# ardunio-physics-board-v3.net
KiCad netlist of a schematic drawn in EAGLE
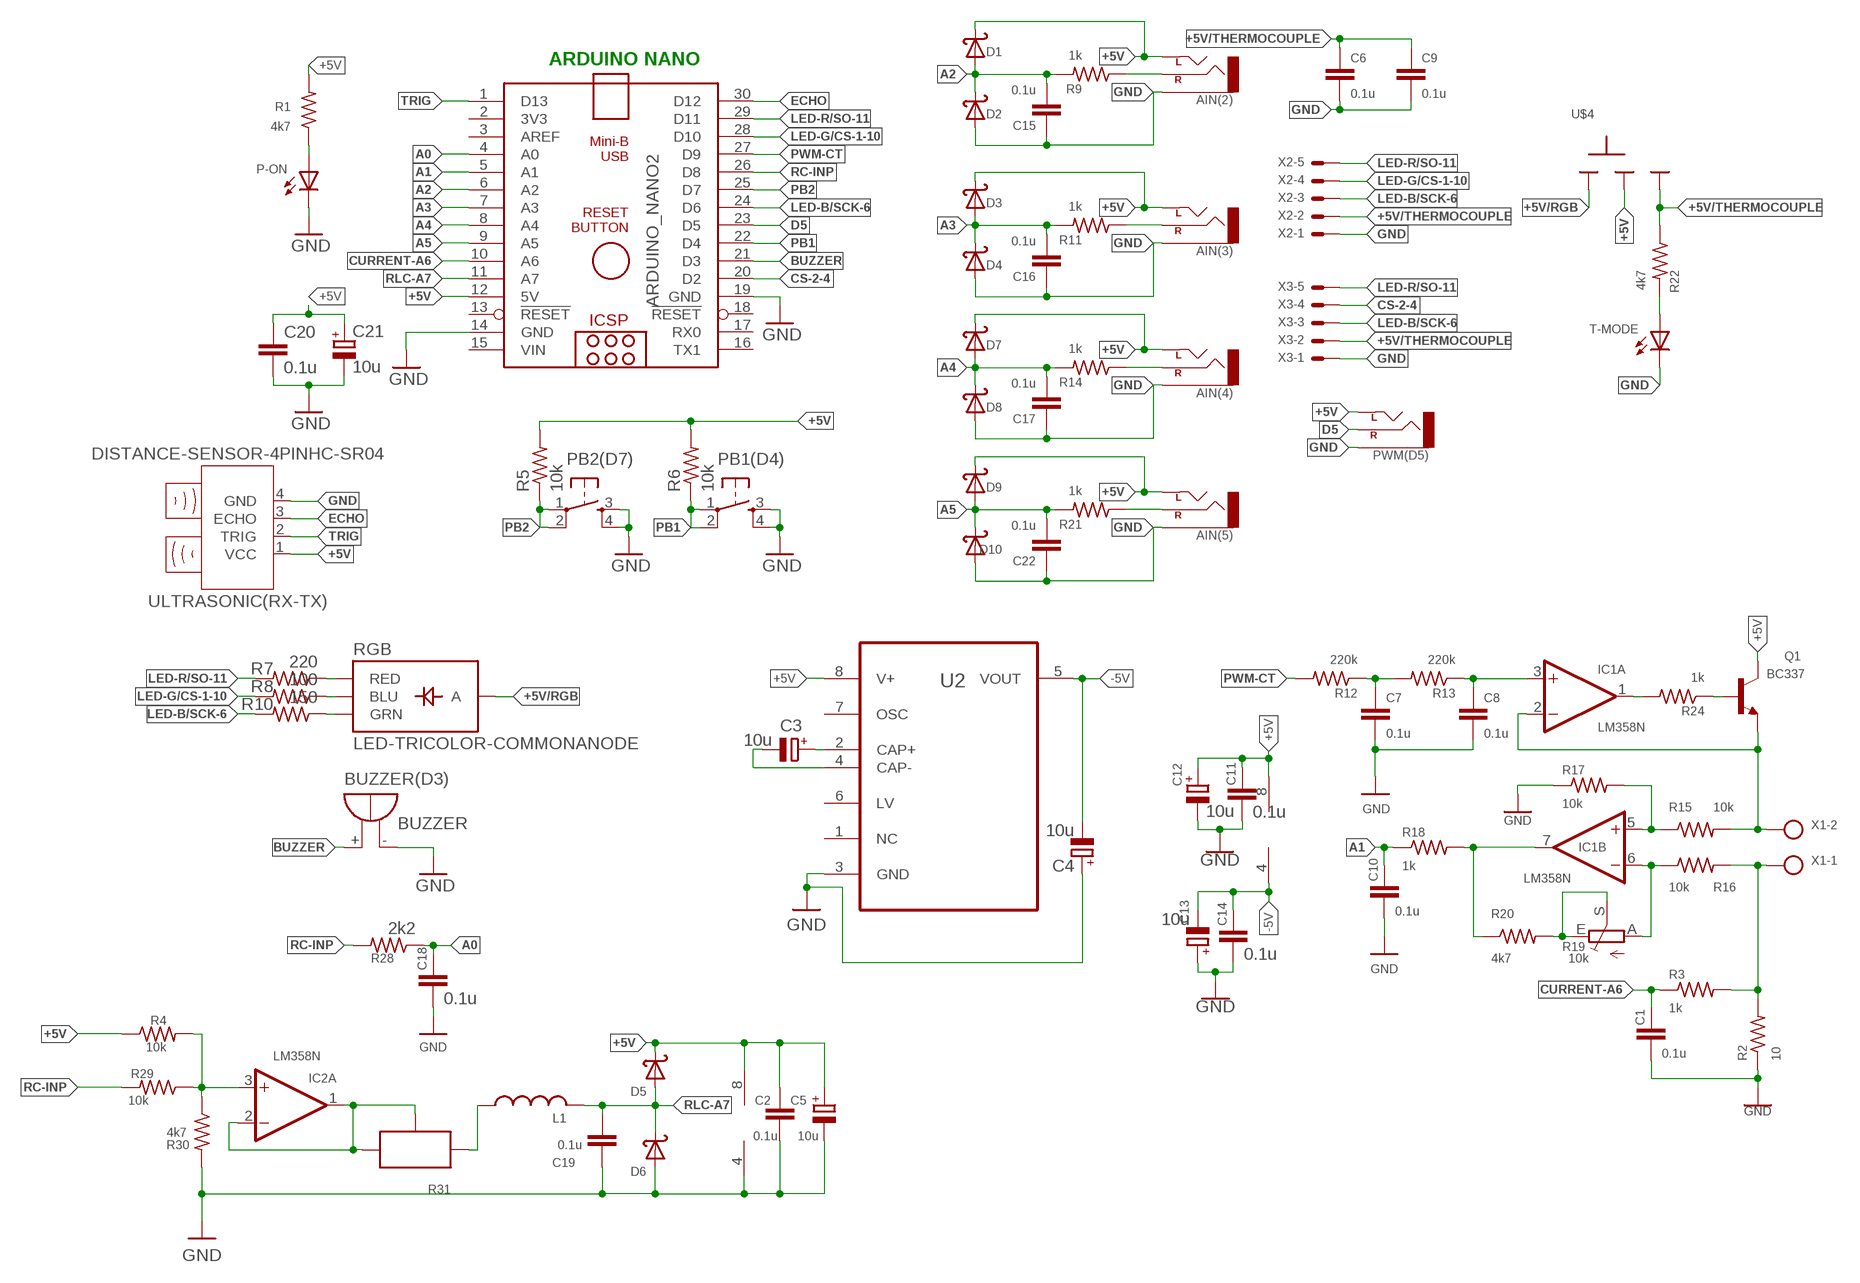
[diagram p0: schematic, sheet 1]

(export (version "E")
  (design (tool "Eeschema 10.0.6"))
  (components
    (comp (ref "AIN(2)")
      (value "AUX-CONNECTOR_CEDT_JANUARY_2015_V5_AUDIO-JACKPTH")
      (footprint "eagle-import:AUX-CONNECTOR_CEDT_JANUARY_2015_V5_AUDIO-JACK")
      (libsource (lib "eagle-import") (part "AUX-CONNECTOR_CEDT_JANUARY_2015_V5_AUDIO-JACKPTH"))
    )
    (comp (ref "AIN(3)")
      (value "AUX-CONNECTOR_CEDT_JANUARY_2015_V5_AUDIO-JACKPTH")
      (footprint "eagle-import:AUX-CONNECTOR_CEDT_JANUARY_2015_V5_AUDIO-JACK")
      (libsource (lib "eagle-import") (part "AUX-CONNECTOR_CEDT_JANUARY_2015_V5_AUDIO-JACKPTH"))
    )
    (comp (ref "AIN(4)")
      (value "AUX-CONNECTOR_CEDT_JANUARY_2015_V5_AUDIO-JACKPTH")
      (footprint "eagle-import:AUX-CONNECTOR_CEDT_JANUARY_2015_V5_AUDIO-JACK")
      (libsource (lib "eagle-import") (part "AUX-CONNECTOR_CEDT_JANUARY_2015_V5_AUDIO-JACKPTH"))
    )
    (comp (ref "AIN(5)")
      (value "AUX-CONNECTOR_CEDT_JANUARY_2015_V5_AUDIO-JACKPTH")
      (footprint "eagle-import:AUX-CONNECTOR_CEDT_JANUARY_2015_V5_AUDIO-JACK")
      (libsource (lib "eagle-import") (part "AUX-CONNECTOR_CEDT_JANUARY_2015_V5_AUDIO-JACKPTH"))
    )
    (comp (ref "ARDUINO_NANO2")
      (value "ARDUINONANOV30_ARDUINO_NANO")
      (footprint "eagle-import:ARDUINONANOV30_ARDUINO_NANO")
      (libsource (lib "eagle-import") (part "ARDUINONANOV30_ARDUINO_NANO"))
    )
    (comp (ref "BUZZER(D3)")
      (value "BUZZER")
      (footprint "eagle-import:F_TMB")
      (libsource (lib "eagle-import") (part "BUZZER"))
    )
    (comp (ref "C1")
      (value "0.1u")
      (footprint "eagle-import:C025-025X050")
      (libsource (lib "eagle-import") (part "C-EU025-025X050"))
    )
    (comp (ref "C2")
      (value "0.1u")
      (footprint "eagle-import:C025-025X050")
      (libsource (lib "eagle-import") (part "C-EU025-025X050"))
    )
    (comp (ref "C3")
      (value "10u")
      (footprint "eagle-import:TT2D5")
      (libsource (lib "eagle-import") (part "CPOL-EUTT2D5"))
    )
    (comp (ref "C4")
      (value "10u")
      (footprint "eagle-import:TT2D5")
      (libsource (lib "eagle-import") (part "CPOL-EUTT2D5"))
    )
    (comp (ref "C5")
      (value "10u")
      (footprint "eagle-import:TT2D5")
      (libsource (lib "eagle-import") (part "CPOL-EUTT2D5"))
    )
    (comp (ref "C6")
      (value "0.1u")
      (footprint "eagle-import:C025-024X044")
      (libsource (lib "eagle-import") (part "C-EU025-024X044"))
    )
    (comp (ref "C7")
      (value "0.1u")
      (footprint "eagle-import:C025-025X050")
      (libsource (lib "eagle-import") (part "C-EU025-025X050"))
    )
    (comp (ref "C8")
      (value "0.1u")
      (footprint "eagle-import:C025-025X050")
      (libsource (lib "eagle-import") (part "C-EU025-025X050"))
    )
    (comp (ref "C9")
      (value "0.1u")
      (footprint "eagle-import:C025-024X044")
      (libsource (lib "eagle-import") (part "C-EU025-024X044"))
    )
    (comp (ref "C10")
      (value "0.1u")
      (footprint "eagle-import:C025-025X050")
      (libsource (lib "eagle-import") (part "C-EU025-025X050"))
    )
    (comp (ref "C11")
      (value "0.1u")
      (footprint "eagle-import:C025-025X050")
      (libsource (lib "eagle-import") (part "C-EU025-025X050"))
    )
    (comp (ref "C12")
      (value "10u")
      (footprint "eagle-import:TT2D5")
      (libsource (lib "eagle-import") (part "CPOL-EUTT2D5"))
    )
    (comp (ref "C13")
      (value "10u")
      (footprint "eagle-import:TT2D5")
      (libsource (lib "eagle-import") (part "CPOL-EUTT2D5"))
    )
    (comp (ref "C14")
      (value "0.1u")
      (footprint "eagle-import:C025-025X050")
      (libsource (lib "eagle-import") (part "C-EU025-025X050"))
    )
    (comp (ref "C15")
      (value "0.1u")
      (footprint "eagle-import:C025-024X044")
      (libsource (lib "eagle-import") (part "C-EU025-024X044"))
    )
    (comp (ref "C16")
      (value "0.1u")
      (footprint "eagle-import:C025-024X044")
      (libsource (lib "eagle-import") (part "C-EU025-024X044"))
    )
    (comp (ref "C17")
      (value "0.1u")
      (footprint "eagle-import:C025-024X044")
      (libsource (lib "eagle-import") (part "C-EU025-024X044"))
    )
    (comp (ref "C18")
      (value "0.1u")
      (footprint "eagle-import:C025-025X050")
      (libsource (lib "eagle-import") (part "C-EU025-025X050"))
    )
    (comp (ref "C19")
      (value "0.1u")
      (footprint "eagle-import:C025-025X050")
      (libsource (lib "eagle-import") (part "C-EU025-025X050"))
    )
    (comp (ref "C20")
      (value "0.1u")
      (footprint "eagle-import:C025-024X044")
      (libsource (lib "eagle-import") (part "C-EU025-024X044"))
    )
    (comp (ref "C21")
      (value "10u")
      (footprint "eagle-import:E2,5-5")
      (libsource (lib "eagle-import") (part "CPOL-EUE2.5-5"))
    )
    (comp (ref "C22")
      (value "0.1u")
      (footprint "eagle-import:C025-024X044")
      (libsource (lib "eagle-import") (part "C-EU025-024X044"))
    )
    (comp (ref "D1")
      (value "1N5819")
      (footprint "eagle-import:DO41-10")
      (libsource (lib "eagle-import") (part "1N5819"))
    )
    (comp (ref "D2")
      (value "1N5819")
      (footprint "eagle-import:DO41-10")
      (libsource (lib "eagle-import") (part "1N5819"))
    )
    (comp (ref "D3")
      (value "1N5819")
      (footprint "eagle-import:DO41-10")
      (libsource (lib "eagle-import") (part "1N5819"))
    )
    (comp (ref "D4")
      (value "1N5819")
      (footprint "eagle-import:DO41-10")
      (libsource (lib "eagle-import") (part "1N5819"))
    )
    (comp (ref "D5")
      (value "1N5819")
      (footprint "eagle-import:DO41-10")
      (libsource (lib "eagle-import") (part "1N5819"))
    )
    (comp (ref "D6")
      (value "1N5819")
      (footprint "eagle-import:DO41-10")
      (libsource (lib "eagle-import") (part "1N5819"))
    )
    (comp (ref "D7")
      (value "1N5819")
      (footprint "eagle-import:DO41-10")
      (libsource (lib "eagle-import") (part "1N5819"))
    )
    (comp (ref "D8")
      (value "1N5819")
      (footprint "eagle-import:DO41-10")
      (libsource (lib "eagle-import") (part "1N5819"))
    )
    (comp (ref "D9")
      (value "1N5819")
      (footprint "eagle-import:DO41-10")
      (libsource (lib "eagle-import") (part "1N5819"))
    )
    (comp (ref "D10")
      (value "1N5819")
      (footprint "eagle-import:DO41-10")
      (libsource (lib "eagle-import") (part "1N5819"))
    )
    (comp (ref "IC1")
      (value "LM358N")
      (footprint "eagle-import:DIL08")
      (libsource (lib "eagle-import") (part "LM358N"))
    )
    (comp (ref "IC2")
      (value "LM358N")
      (footprint "eagle-import:DIL08")
      (libsource (lib "eagle-import") (part "LM358N"))
    )
    (comp (ref "L1")
      (value "L-US6000-XXX-RC")
      (footprint "eagle-import:6000-XXXX-RC")
      (libsource (lib "eagle-import") (part "L-US6000-XXX-RC"))
    )
    (comp (ref "P-ON")
      (value "LED3MM")
      (footprint "eagle-import:LED3MM")
      (libsource (lib "eagle-import") (part "LED3MM"))
    )
    (comp (ref "PB1(D4)")
      (value "OMRON_SWITCH_40-XX")
      (footprint "eagle-import:B3F-40XX")
      (libsource (lib "eagle-import") (part "OMRON_SWITCH_40-XX"))
    )
    (comp (ref "PB2(D7)")
      (value "OMRON_SWITCH_40-XX")
      (footprint "eagle-import:B3F-40XX")
      (libsource (lib "eagle-import") (part "OMRON_SWITCH_40-XX"))
    )
    (comp (ref "PWM(D5)")
      (value "AUX-CONNECTOR_CEDT_JANUARY_2015_V5_AUDIO-JACKPTH")
      (footprint "eagle-import:AUX-CONNECTOR_CEDT_JANUARY_2015_V5_AUDIO-JACK")
      (libsource (lib "eagle-import") (part "AUX-CONNECTOR_CEDT_JANUARY_2015_V5_AUDIO-JACKPTH"))
    )
    (comp (ref "Q1")
      (value "BC337")
      (footprint "eagle-import:TO92")
      (libsource (lib "eagle-import") (part "BC337"))
    )
    (comp (ref "R1")
      (value "4k7")
      (footprint "eagle-import:0204_7")
      (libsource (lib "eagle-import") (part "R-US_0204/7"))
    )
    (comp (ref "R2")
      (value "10")
      (footprint "eagle-import:0207_10")
      (libsource (lib "eagle-import") (part "RESISTOR0207/10"))
    )
    (comp (ref "R3")
      (value "1k")
      (footprint "eagle-import:0204_7")
      (libsource (lib "eagle-import") (part "R-US_0204/7"))
    )
    (comp (ref "R4")
      (value "10k")
      (footprint "eagle-import:0207_10")
      (libsource (lib "eagle-import") (part "R-US_0207/10"))
    )
    (comp (ref "R5")
      (value "10k")
      (footprint "eagle-import:0204_7")
      (libsource (lib "eagle-import") (part "R-US_0204/7"))
    )
    (comp (ref "R6")
      (value "10k")
      (footprint "eagle-import:0204_7")
      (libsource (lib "eagle-import") (part "R-US_0204/7"))
    )
    (comp (ref "R7")
      (value "220")
      (footprint "eagle-import:0207_10")
      (libsource (lib "eagle-import") (part "R-US_0207/10"))
    )
    (comp (ref "R8")
      (value "100")
      (footprint "eagle-import:0207_10")
      (libsource (lib "eagle-import") (part "R-US_0207/10"))
    )
    (comp (ref "R9")
      (value "1k")
      (footprint "eagle-import:0204_7")
      (libsource (lib "eagle-import") (part "R-US_0204/7"))
    )
    (comp (ref "R10")
      (value "150")
      (footprint "eagle-import:0207_10")
      (libsource (lib "eagle-import") (part "R-US_0207/10"))
    )
    (comp (ref "R11")
      (value "1k")
      (footprint "eagle-import:0204_7")
      (libsource (lib "eagle-import") (part "R-US_0204/7"))
    )
    (comp (ref "R12")
      (value "220k")
      (footprint "eagle-import:0207_10")
      (libsource (lib "eagle-import") (part "R-US_0207/10"))
    )
    (comp (ref "R13")
      (value "220k")
      (footprint "eagle-import:0204_7")
      (libsource (lib "eagle-import") (part "R-US_0204/7"))
    )
    (comp (ref "R14")
      (value "1k")
      (footprint "eagle-import:0204_7")
      (libsource (lib "eagle-import") (part "R-US_0204/7"))
    )
    (comp (ref "R15")
      (value "10k")
      (footprint "eagle-import:0204_7")
      (libsource (lib "eagle-import") (part "R-US_0204/7"))
    )
    (comp (ref "R16")
      (value "10k")
      (footprint "eagle-import:0204_7")
      (libsource (lib "eagle-import") (part "R-US_0204/7"))
    )
    (comp (ref "R17")
      (value "10k")
      (footprint "eagle-import:0204_7")
      (libsource (lib "eagle-import") (part "R-US_0204/7"))
    )
    (comp (ref "R18")
      (value "1k")
      (footprint "eagle-import:0204_7")
      (libsource (lib "eagle-import") (part "R-US_0204/7"))
    )
    (comp (ref "R19")
      (value "10k")
      (footprint "eagle-import:RJ9W")
      (libsource (lib "eagle-import") (part "TRIM_EU-RJ9W"))
    )
    (comp (ref "R20")
      (value "4k7")
      (footprint "eagle-import:0204_7")
      (libsource (lib "eagle-import") (part "R-US_0204/7"))
    )
    (comp (ref "R21")
      (value "1k")
      (footprint "eagle-import:0204_7")
      (libsource (lib "eagle-import") (part "R-US_0204/7"))
    )
    (comp (ref "R22")
      (value "4k7")
      (footprint "eagle-import:0204_7")
      (libsource (lib "eagle-import") (part "R-US_0204/7"))
    )
    (comp (ref "R24")
      (value "1k")
      (footprint "eagle-import:0204_7")
      (libsource (lib "eagle-import") (part "R-US_0204/7"))
    )
    (comp (ref "R28")
      (value "2k2")
      (footprint "eagle-import:0207_10")
      (libsource (lib "eagle-import") (part "R-US_0207/10"))
    )
    (comp (ref "R29")
      (value "10k")
      (footprint "eagle-import:0204_7")
      (libsource (lib "eagle-import") (part "R-US_0204/7"))
    )
    (comp (ref "R30")
      (value "4k7")
      (footprint "eagle-import:0207_10")
      (libsource (lib "eagle-import") (part "R-US_0207/10"))
    )
    (comp (ref "R31")
      (value "POTNORMAL")
      (footprint "eagle-import:RJ9W")
      (libsource (lib "eagle-import") (part "POTNORMAL"))
    )
    (comp (ref "RGB")
      (value "LED-TRICOLOR-COMMONANODE")
      (footprint "eagle-import:LED-TRICOLOR-THROUGHHOLE")
      (libsource (lib "eagle-import") (part "LED-TRICOLOR-COMMONANODE"))
    )
    (comp (ref "T-MODE")
      (value "LED3MM")
      (footprint "eagle-import:LED3MM")
      (libsource (lib "eagle-import") (part "LED3MM"))
    )
    (comp (ref "U$4")
      (value "SLIDESWITCH-BIG")
      (footprint "eagle-import:BIGSWITCH")
      (libsource (lib "eagle-import") (part "SLIDESWITCH-BIG"))
    )
    (comp (ref "U2")
      (value "ICL7660CPAZ_ICL7660CPAZ")
      (footprint "eagle-import:ICL7660CPAZ_DIP254P762X533-8")
      (fields (field (name "MF") "Renesas Electronics") (field (name "MP") "ICL7660CPAZ"))
      (libsource (lib "eagle-import") (part "ICL7660CPAZ_ICL7660CPAZ"))
    )
    (comp (ref "ULTRASONIC(RX-TX)")
      (value "DISTANCE-SENSOR-4PINHC-SR04")
      (footprint "eagle-import:HC-SR04")
      (libsource (lib "eagle-import") (part "DISTANCE-SENSOR-4PINHC-SR04"))
    )
    (comp (ref "X1")
      (value "AK500/2-H")
      (footprint "eagle-import:AK500_2-H")
      (libsource (lib "eagle-import") (part "AK500/2-H"))
    )
    (comp (ref "X2")
      (value "JST-XH-05-PIN-LONG-PAD")
      (footprint "eagle-import:JST-XH-05-PACKAGE-LONG-PAD")
      (libsource (lib "eagle-import") (part "JST-XH-05-PIN-LONG-PAD"))
    )
    (comp (ref "X3")
      (value "JST-XH-05-PIN-LONG-PAD")
      (footprint "eagle-import:JST-XH-05-PACKAGE-LONG-PAD")
      (libsource (lib "eagle-import") (part "JST-XH-05-PIN-LONG-PAD"))
    )
  )
  (nets
    (net (code "1") (name "+5V") (class "Default")
      (node (ref "AIN(2)") (pin "TIP") (pinfunction "LEFT_TIP") (pintype "bidirectional"))
      (node (ref "AIN(3)") (pin "TIP") (pinfunction "LEFT_TIP") (pintype "bidirectional"))
      (node (ref "AIN(4)") (pin "TIP") (pinfunction "LEFT_TIP") (pintype "bidirectional"))
      (node (ref "AIN(5)") (pin "TIP") (pinfunction "LEFT_TIP") (pintype "bidirectional"))
      (node (ref "ARDUINO_NANO2") (pin "12") (pinfunction "5V_12") (pintype "power_in"))
      (node (ref "C11") (pin "1") (pinfunction "1_1") (pintype "passive"))
      (node (ref "C12") (pin "+") (pinfunction "+_+") (pintype "passive"))
      (node (ref "C2") (pin "1") (pinfunction "1_1") (pintype "passive"))
      (node (ref "C20") (pin "1") (pinfunction "1_1") (pintype "passive"))
      (node (ref "C21") (pin "+") (pinfunction "+_+") (pintype "passive"))
      (node (ref "C5") (pin "+") (pinfunction "+_+") (pintype "passive"))
      (node (ref "D1") (pin "C") (pinfunction "C_C") (pintype "passive"))
      (node (ref "D3") (pin "C") (pinfunction "C_C") (pintype "passive"))
      (node (ref "D5") (pin "C") (pinfunction "C_C") (pintype "passive"))
      (node (ref "D7") (pin "C") (pinfunction "C_C") (pintype "passive"))
      (node (ref "D9") (pin "C") (pinfunction "C_C") (pintype "passive"))
      (node (ref "IC1") (pin "8") (pinfunction "V+_8") (pintype "power_in"))
      (node (ref "IC2") (pin "8") (pinfunction "V+_8") (pintype "power_in"))
      (node (ref "PWM(D5)") (pin "TIP") (pinfunction "LEFT_TIP") (pintype "bidirectional"))
      (node (ref "Q1") (pin "3") (pinfunction "C_3") (pintype "passive"))
      (node (ref "R1") (pin "2") (pinfunction "2_2") (pintype "passive"))
      (node (ref "R4") (pin "1") (pinfunction "1_1") (pintype "passive"))
      (node (ref "R5") (pin "2") (pinfunction "2_2") (pintype "passive"))
      (node (ref "R6") (pin "2") (pinfunction "2_2") (pintype "passive"))
      (node (ref "U$4") (pin "2") (pinfunction "2_2") (pintype "bidirectional"))
      (node (ref "U2") (pin "8") (pinfunction "V+_8") (pintype "power_in"))
      (node (ref "ULTRASONIC(RX-TX)") (pin "1") (pinfunction "VCC_1") (pintype "bidirectional"))
    )
    (net (code "2") (name "+5V{slash}RGB") (class "Default")
      (node (ref "RGB") (pin "ANODE") (pinfunction "A_ANODE") (pintype "bidirectional"))
      (node (ref "U$4") (pin "1") (pinfunction "1_1") (pintype "bidirectional"))
    )
    (net (code "3") (name "+5V{slash}THERMOCOUPLE") (class "Default")
      (node (ref "C6") (pin "1") (pinfunction "1_1") (pintype "passive"))
      (node (ref "C9") (pin "1") (pinfunction "1_1") (pintype "passive"))
      (node (ref "R22") (pin "1") (pinfunction "1_1") (pintype "passive"))
      (node (ref "U$4") (pin "3") (pinfunction "3_3") (pintype "bidirectional"))
      (node (ref "X2") (pin "2") (pinfunction "S_2") (pintype "passive"))
      (node (ref "X3") (pin "2") (pinfunction "S_2") (pintype "passive"))
    )
    (net (code "4") (name "-5V") (class "Default")
      (node (ref "C13") (pin "-") (pinfunction "-_-") (pintype "passive"))
      (node (ref "C14") (pin "1") (pinfunction "1_1") (pintype "passive"))
      (node (ref "C4") (pin "-") (pinfunction "-_-") (pintype "passive"))
      (node (ref "IC1") (pin "4") (pinfunction "V-_4") (pintype "power_in"))
      (node (ref "U2") (pin "5") (pinfunction "VOUT_5") (pintype "output"))
    )
    (net (code "5") (name "/VIN") (class "Default")
      (node (ref "ARDUINO_NANO2") (pin "15") (pinfunction "VIN_15") (pintype "power_in"))
    )
    (net (code "6") (name "A0") (class "Default")
      (node (ref "ARDUINO_NANO2") (pin "4") (pinfunction "A0_4") (pintype "bidirectional"))
      (node (ref "C18") (pin "1") (pinfunction "1_1") (pintype "passive"))
      (node (ref "R28") (pin "1") (pinfunction "1_1") (pintype "passive"))
    )
    (net (code "7") (name "A1") (class "Default")
      (node (ref "ARDUINO_NANO2") (pin "5") (pinfunction "A1_5") (pintype "bidirectional"))
      (node (ref "C10") (pin "1") (pinfunction "1_1") (pintype "passive"))
      (node (ref "R18") (pin "1") (pinfunction "1_1") (pintype "passive"))
    )
    (net (code "8") (name "A2") (class "Default")
      (node (ref "ARDUINO_NANO2") (pin "6") (pinfunction "A2_6") (pintype "bidirectional"))
      (node (ref "C15") (pin "2") (pinfunction "2_2") (pintype "passive"))
      (node (ref "D1") (pin "A") (pinfunction "A_A") (pintype "passive"))
      (node (ref "D2") (pin "C") (pinfunction "C_C") (pintype "passive"))
      (node (ref "R9") (pin "2") (pinfunction "2_2") (pintype "passive"))
    )
    (net (code "9") (name "A3") (class "Default")
      (node (ref "ARDUINO_NANO2") (pin "7") (pinfunction "A3_7") (pintype "bidirectional"))
      (node (ref "C16") (pin "2") (pinfunction "2_2") (pintype "passive"))
      (node (ref "D3") (pin "A") (pinfunction "A_A") (pintype "passive"))
      (node (ref "D4") (pin "C") (pinfunction "C_C") (pintype "passive"))
      (node (ref "R11") (pin "2") (pinfunction "2_2") (pintype "passive"))
    )
    (net (code "10") (name "A4") (class "Default")
      (node (ref "ARDUINO_NANO2") (pin "8") (pinfunction "A4_8") (pintype "bidirectional"))
      (node (ref "C17") (pin "2") (pinfunction "2_2") (pintype "passive"))
      (node (ref "D7") (pin "A") (pinfunction "A_A") (pintype "passive"))
      (node (ref "D8") (pin "C") (pinfunction "C_C") (pintype "passive"))
      (node (ref "R14") (pin "2") (pinfunction "2_2") (pintype "passive"))
    )
    (net (code "11") (name "A5") (class "Default")
      (node (ref "ARDUINO_NANO2") (pin "9") (pinfunction "A5_9") (pintype "bidirectional"))
      (node (ref "C22") (pin "2") (pinfunction "2_2") (pintype "passive"))
      (node (ref "D10") (pin "C") (pinfunction "C_C") (pintype "passive"))
      (node (ref "D9") (pin "A") (pinfunction "A_A") (pintype "passive"))
      (node (ref "R21") (pin "2") (pinfunction "2_2") (pintype "passive"))
    )
    (net (code "12") (name "BUZZER") (class "Default")
      (node (ref "ARDUINO_NANO2") (pin "21") (pinfunction "D3_21") (pintype "bidirectional"))
      (node (ref "BUZZER(D3)") (pin "+") (pinfunction "+_+") (pintype "passive"))
    )
    (net (code "13") (name "CS-2-4") (class "Default")
      (node (ref "ARDUINO_NANO2") (pin "20") (pinfunction "D2_20") (pintype "bidirectional"))
      (node (ref "X3") (pin "4") (pinfunction "S_4") (pintype "passive"))
    )
    (net (code "14") (name "CURRENT-A6") (class "Default")
      (node (ref "ARDUINO_NANO2") (pin "10") (pinfunction "A6_10") (pintype "bidirectional"))
      (node (ref "C1") (pin "1") (pinfunction "1_1") (pintype "passive"))
      (node (ref "R3") (pin "1") (pinfunction "1_1") (pintype "passive"))
    )
    (net (code "15") (name "D5") (class "Default")
      (node (ref "ARDUINO_NANO2") (pin "23") (pinfunction "D5_23") (pintype "bidirectional"))
      (node (ref "PWM(D5)") (pin "RING") (pinfunction "RIGHT_RING") (pintype "bidirectional"))
    )
    (net (code "16") (name "ECHO") (class "Default")
      (node (ref "ARDUINO_NANO2") (pin "30") (pinfunction "D12_30") (pintype "bidirectional"))
      (node (ref "ULTRASONIC(RX-TX)") (pin "3") (pinfunction "ECHO_3") (pintype "bidirectional"))
    )
    (net (code "17") (name "GND") (class "Default")
      (node (ref "AIN(2)") (pin "SLEEVE") (pinfunction "SLEEVE_SLEEVE") (pintype "bidirectional"))
      (node (ref "AIN(3)") (pin "SLEEVE") (pinfunction "SLEEVE_SLEEVE") (pintype "bidirectional"))
      (node (ref "AIN(4)") (pin "SLEEVE") (pinfunction "SLEEVE_SLEEVE") (pintype "bidirectional"))
      (node (ref "AIN(5)") (pin "SLEEVE") (pinfunction "SLEEVE_SLEEVE") (pintype "bidirectional"))
      (node (ref "ARDUINO_NANO2") (pin "14") (pinfunction "GND_14") (pintype "power_in"))
      (node (ref "ARDUINO_NANO2") (pin "19") (pinfunction "GND_19") (pintype "power_in"))
      (node (ref "BUZZER(D3)") (pin "-") (pinfunction "-_-") (pintype "passive"))
      (node (ref "C1") (pin "2") (pinfunction "2_2") (pintype "passive"))
      (node (ref "C10") (pin "2") (pinfunction "2_2") (pintype "passive"))
      (node (ref "C11") (pin "2") (pinfunction "2_2") (pintype "passive"))
      (node (ref "C12") (pin "-") (pinfunction "-_-") (pintype "passive"))
      (node (ref "C13") (pin "+") (pinfunction "+_+") (pintype "passive"))
      (node (ref "C14") (pin "2") (pinfunction "2_2") (pintype "passive"))
      (node (ref "C15") (pin "1") (pinfunction "1_1") (pintype "passive"))
      (node (ref "C16") (pin "1") (pinfunction "1_1") (pintype "passive"))
      (node (ref "C17") (pin "1") (pinfunction "1_1") (pintype "passive"))
      (node (ref "C18") (pin "2") (pinfunction "2_2") (pintype "passive"))
      (node (ref "C19") (pin "2") (pinfunction "2_2") (pintype "passive"))
      (node (ref "C2") (pin "2") (pinfunction "2_2") (pintype "passive"))
      (node (ref "C20") (pin "2") (pinfunction "2_2") (pintype "passive"))
      (node (ref "C21") (pin "-") (pinfunction "-_-") (pintype "passive"))
      (node (ref "C22") (pin "1") (pinfunction "1_1") (pintype "passive"))
      (node (ref "C4") (pin "+") (pinfunction "+_+") (pintype "passive"))
      (node (ref "C5") (pin "-") (pinfunction "-_-") (pintype "passive"))
      (node (ref "C6") (pin "2") (pinfunction "2_2") (pintype "passive"))
      (node (ref "C7") (pin "2") (pinfunction "2_2") (pintype "passive"))
      (node (ref "C8") (pin "2") (pinfunction "2_2") (pintype "passive"))
      (node (ref "C9") (pin "2") (pinfunction "2_2") (pintype "passive"))
      (node (ref "D10") (pin "A") (pinfunction "A_A") (pintype "passive"))
      (node (ref "D2") (pin "A") (pinfunction "A_A") (pintype "passive"))
      (node (ref "D4") (pin "A") (pinfunction "A_A") (pintype "passive"))
      (node (ref "D6") (pin "A") (pinfunction "A_A") (pintype "passive"))
      (node (ref "D8") (pin "A") (pinfunction "A_A") (pintype "passive"))
      (node (ref "IC2") (pin "4") (pinfunction "V-_4") (pintype "power_in"))
      (node (ref "P-ON") (pin "K") (pinfunction "C_K") (pintype "passive"))
      (node (ref "PB1(D4)") (pin "3") (pinfunction "S_3") (pintype "passive"))
      (node (ref "PB1(D4)") (pin "4") (pinfunction "S1_4") (pintype "passive"))
      (node (ref "PB2(D7)") (pin "3") (pinfunction "S_3") (pintype "passive"))
      (node (ref "PB2(D7)") (pin "4") (pinfunction "S1_4") (pintype "passive"))
      (node (ref "PWM(D5)") (pin "SLEEVE") (pinfunction "SLEEVE_SLEEVE") (pintype "bidirectional"))
      (node (ref "R17") (pin "1") (pinfunction "1_1") (pintype "passive"))
      (node (ref "R2") (pin "1") (pinfunction "1_1") (pintype "passive"))
      (node (ref "R30") (pin "2") (pinfunction "2_2") (pintype "passive"))
      (node (ref "T-MODE") (pin "K") (pinfunction "C_K") (pintype "passive"))
      (node (ref "U2") (pin "3") (pinfunction "GND_3") (pintype "passive"))
      (node (ref "ULTRASONIC(RX-TX)") (pin "4") (pinfunction "GND_4") (pintype "bidirectional"))
      (node (ref "X2") (pin "1") (pinfunction "S_1") (pintype "passive"))
      (node (ref "X3") (pin "1") (pinfunction "S_1") (pintype "passive"))
    )
    (net (code "18") (name "LED-B{slash}SCK-6") (class "Default")
      (node (ref "ARDUINO_NANO2") (pin "24") (pinfunction "D6_24") (pintype "bidirectional"))
      (node (ref "R10") (pin "2") (pinfunction "2_2") (pintype "passive"))
      (node (ref "X2") (pin "3") (pinfunction "S_3") (pintype "passive"))
      (node (ref "X3") (pin "3") (pinfunction "S_3") (pintype "passive"))
    )
    (net (code "19") (name "LED-G{slash}CS-1-10") (class "Default")
      (node (ref "ARDUINO_NANO2") (pin "28") (pinfunction "D10_28") (pintype "bidirectional"))
      (node (ref "R8") (pin "2") (pinfunction "2_2") (pintype "passive"))
      (node (ref "X2") (pin "4") (pinfunction "S_4") (pintype "passive"))
    )
    (net (code "20") (name "LED-R{slash}SO-11") (class "Default")
      (node (ref "ARDUINO_NANO2") (pin "29") (pinfunction "D11_29") (pintype "bidirectional"))
      (node (ref "R7") (pin "2") (pinfunction "2_2") (pintype "passive"))
      (node (ref "X2") (pin "5") (pinfunction "S_5") (pintype "passive"))
      (node (ref "X3") (pin "5") (pinfunction "S_5") (pintype "passive"))
    )
    (net (code "21") (name "Net-(AIN(2)-RIGHT)") (class "Default")
      (node (ref "AIN(2)") (pin "RING") (pinfunction "RIGHT_RING") (pintype "bidirectional"))
      (node (ref "R9") (pin "1") (pinfunction "1_1") (pintype "passive"))
    )
    (net (code "22") (name "Net-(AIN(3)-RIGHT)") (class "Default")
      (node (ref "AIN(3)") (pin "RING") (pinfunction "RIGHT_RING") (pintype "bidirectional"))
      (node (ref "R11") (pin "1") (pinfunction "1_1") (pintype "passive"))
    )
    (net (code "23") (name "Net-(AIN(4)-RIGHT)") (class "Default")
      (node (ref "AIN(4)") (pin "RING") (pinfunction "RIGHT_RING") (pintype "bidirectional"))
      (node (ref "R14") (pin "1") (pinfunction "1_1") (pintype "passive"))
    )
    (net (code "24") (name "Net-(AIN(5)-RIGHT)") (class "Default")
      (node (ref "AIN(5)") (pin "RING") (pinfunction "RIGHT_RING") (pintype "bidirectional"))
      (node (ref "R21") (pin "1") (pinfunction "1_1") (pintype "passive"))
    )
    (net (code "25") (name "Net-(C7-Pad1)") (class "Default")
      (node (ref "C7") (pin "1") (pinfunction "1_1") (pintype "passive"))
      (node (ref "R12") (pin "1") (pinfunction "1_1") (pintype "passive"))
      (node (ref "R13") (pin "2") (pinfunction "2_2") (pintype "passive"))
    )
    (net (code "26") (name "Net-(IC1A-+IN)") (class "Default")
      (node (ref "C8") (pin "1") (pinfunction "1_1") (pintype "passive"))
      (node (ref "IC1") (pin "3") (pinfunction "+IN_3") (pintype "input"))
      (node (ref "R13") (pin "1") (pinfunction "1_1") (pintype "passive"))
    )
    (net (code "27") (name "Net-(IC1A--IN)") (class "Default")
      (node (ref "IC1") (pin "2") (pinfunction "-IN_2") (pintype "input"))
      (node (ref "Q1") (pin "1") (pinfunction "E_1") (pintype "passive"))
      (node (ref "R15") (pin "2") (pinfunction "2_2") (pintype "passive"))
      (node (ref "X1") (pin "2") (pinfunction "KL_2") (pintype "passive"))
    )
    (net (code "28") (name "Net-(IC1A-OUT)") (class "Default")
      (node (ref "IC1") (pin "1") (pinfunction "OUT_1") (pintype "output"))
      (node (ref "R24") (pin "2") (pinfunction "2_2") (pintype "passive"))
    )
    (net (code "29") (name "Net-(IC1B-+IN)") (class "Default")
      (node (ref "IC1") (pin "5") (pinfunction "+IN_5") (pintype "input"))
      (node (ref "R15") (pin "1") (pinfunction "1_1") (pintype "passive"))
      (node (ref "R17") (pin "2") (pinfunction "2_2") (pintype "passive"))
    )
    (net (code "30") (name "Net-(IC1B--IN)") (class "Default")
      (node (ref "IC1") (pin "6") (pinfunction "-IN_6") (pintype "input"))
      (node (ref "R16") (pin "1") (pinfunction "1_1") (pintype "passive"))
      (node (ref "R19") (pin "A") (pinfunction "A_A") (pintype "passive"))
    )
    (net (code "31") (name "Net-(IC1B-OUT)") (class "Default")
      (node (ref "IC1") (pin "7") (pinfunction "OUT_7") (pintype "output"))
      (node (ref "R18") (pin "2") (pinfunction "2_2") (pintype "passive"))
      (node (ref "R20") (pin "1") (pinfunction "1_1") (pintype "passive"))
    )
    (net (code "32") (name "Net-(IC2A-+IN)") (class "Default")
      (node (ref "IC2") (pin "3") (pinfunction "+IN_3") (pintype "input"))
      (node (ref "R29") (pin "1") (pinfunction "1_1") (pintype "passive"))
      (node (ref "R30") (pin "1") (pinfunction "1_1") (pintype "passive"))
      (node (ref "R4") (pin "2") (pinfunction "2_2") (pintype "passive"))
    )
    (net (code "33") (name "Net-(IC2A--IN)") (class "Default")
      (node (ref "IC2") (pin "1") (pinfunction "OUT_1") (pintype "output"))
      (node (ref "IC2") (pin "2") (pinfunction "-IN_2") (pintype "input"))
      (node (ref "R31") (pin "A") (pinfunction "A_A") (pintype "passive"))
      (node (ref "R31") (pin "S") (pinfunction "S_S") (pintype "passive"))
    )
    (net (code "34") (name "Net-(L1-Pad1)") (class "Default")
      (node (ref "L1") (pin "1") (pinfunction "1_1") (pintype "passive"))
      (node (ref "R31") (pin "E") (pinfunction "E_E") (pintype "passive"))
    )
    (net (code "35") (name "Net-(P-ON-PadA)") (class "Default")
      (node (ref "P-ON") (pin "A") (pinfunction "A_A") (pintype "passive"))
      (node (ref "R1") (pin "1") (pinfunction "1_1") (pintype "passive"))
    )
    (net (code "36") (name "Net-(Q1-B)") (class "Default")
      (node (ref "Q1") (pin "2") (pinfunction "B_2") (pintype "passive"))
      (node (ref "R24") (pin "1") (pinfunction "1_1") (pintype "passive"))
    )
    (net (code "37") (name "Net-(R7-Pad1)") (class "Default")
      (node (ref "R7") (pin "1") (pinfunction "1_1") (pintype "passive"))
      (node (ref "RGB") (pin "RED") (pinfunction "RED_RED") (pintype "bidirectional"))
    )
    (net (code "38") (name "Net-(R8-Pad1)") (class "Default")
      (node (ref "R8") (pin "1") (pinfunction "1_1") (pintype "passive"))
      (node (ref "RGB") (pin "BLU") (pinfunction "BLU_BLU") (pintype "bidirectional"))
    )
    (net (code "39") (name "Net-(R10-Pad1)") (class "Default")
      (node (ref "R10") (pin "1") (pinfunction "1_1") (pintype "passive"))
      (node (ref "RGB") (pin "GRN") (pinfunction "GRN_GRN") (pintype "bidirectional"))
    )
    (net (code "40") (name "Net-(R19-PadE)") (class "Default")
      (node (ref "R19") (pin "E") (pinfunction "E_E") (pintype "passive"))
      (node (ref "R19") (pin "S") (pinfunction "S_S") (pintype "passive"))
      (node (ref "R20") (pin "2") (pinfunction "2_2") (pintype "passive"))
    )
    (net (code "41") (name "Net-(R22-Pad2)") (class "Default")
      (node (ref "R22") (pin "2") (pinfunction "2_2") (pintype "passive"))
      (node (ref "T-MODE") (pin "A") (pinfunction "A_A") (pintype "passive"))
    )
    (net (code "42") (name "Net-(U2-CAP+)") (class "Default")
      (node (ref "C3") (pin "+") (pinfunction "+_+") (pintype "passive"))
      (node (ref "U2") (pin "2") (pinfunction "CAP+_2") (pintype "input"))
    )
    (net (code "43") (name "Net-(U2-CAP-)") (class "Default")
      (node (ref "C3") (pin "-") (pinfunction "-_-") (pintype "passive"))
      (node (ref "U2") (pin "4") (pinfunction "CAP-_4") (pintype "input"))
    )
    (net (code "44") (name "Net-(X1A-KL)") (class "Default")
      (node (ref "R16") (pin "2") (pinfunction "2_2") (pintype "passive"))
      (node (ref "R2") (pin "2") (pinfunction "2_2") (pintype "passive"))
      (node (ref "R3") (pin "2") (pinfunction "2_2") (pintype "passive"))
      (node (ref "X1") (pin "1") (pinfunction "KL_1") (pintype "passive"))
    )
    (net (code "45") (name "PB1") (class "Default")
      (node (ref "ARDUINO_NANO2") (pin "22") (pinfunction "D4_22") (pintype "bidirectional"))
      (node (ref "PB1(D4)") (pin "1") (pinfunction "P_1") (pintype "passive"))
      (node (ref "PB1(D4)") (pin "2") (pinfunction "P1_2") (pintype "passive"))
      (node (ref "R6") (pin "1") (pinfunction "1_1") (pintype "passive"))
    )
    (net (code "46") (name "PB2") (class "Default")
      (node (ref "ARDUINO_NANO2") (pin "25") (pinfunction "D7_25") (pintype "bidirectional"))
      (node (ref "PB2(D7)") (pin "1") (pinfunction "P_1") (pintype "passive"))
      (node (ref "PB2(D7)") (pin "2") (pinfunction "P1_2") (pintype "passive"))
      (node (ref "R5") (pin "1") (pinfunction "1_1") (pintype "passive"))
    )
    (net (code "47") (name "PWM-CT") (class "Default")
      (node (ref "ARDUINO_NANO2") (pin "27") (pinfunction "D9_27") (pintype "bidirectional"))
      (node (ref "R12") (pin "2") (pinfunction "2_2") (pintype "passive"))
    )
    (net (code "48") (name "RC-INP") (class "Default")
      (node (ref "ARDUINO_NANO2") (pin "26") (pinfunction "D8_26") (pintype "bidirectional"))
      (node (ref "R28") (pin "2") (pinfunction "2_2") (pintype "passive"))
      (node (ref "R29") (pin "2") (pinfunction "2_2") (pintype "passive"))
    )
    (net (code "49") (name "RLC-A7") (class "Default")
      (node (ref "ARDUINO_NANO2") (pin "11") (pinfunction "A7_11") (pintype "bidirectional"))
      (node (ref "C19") (pin "1") (pinfunction "1_1") (pintype "passive"))
      (node (ref "D5") (pin "A") (pinfunction "A_A") (pintype "passive"))
      (node (ref "D6") (pin "C") (pinfunction "C_C") (pintype "passive"))
      (node (ref "L1") (pin "2") (pinfunction "2_2") (pintype "passive"))
    )
    (net (code "50") (name "TRIG") (class "Default")
      (node (ref "ARDUINO_NANO2") (pin "1") (pinfunction "D13_1") (pintype "bidirectional"))
      (node (ref "ULTRASONIC(RX-TX)") (pin "2") (pinfunction "TRIG_2") (pintype "bidirectional"))
    )
    (net (code "51") (name "unconnected-(ARDUINO_NANO2-3V3-Pad2)") (class "Default")
      (node (ref "ARDUINO_NANO2") (pin "2") (pinfunction "3V3_2") (pintype "output"))
    )
    (net (code "52") (name "unconnected-(ARDUINO_NANO2-AREF-Pad3)") (class "Default")
      (node (ref "ARDUINO_NANO2") (pin "3") (pinfunction "AREF_3") (pintype "input"))
    )
    (net (code "53") (name "unconnected-(ARDUINO_NANO2-RX0-Pad17)") (class "Default")
      (node (ref "ARDUINO_NANO2") (pin "17") (pinfunction "RX0_17") (pintype "bidirectional"))
    )
    (net (code "54") (name "unconnected-(ARDUINO_NANO2-TX1-Pad16)") (class "Default")
      (node (ref "ARDUINO_NANO2") (pin "16") (pinfunction "TX1_16") (pintype "bidirectional"))
    )
    (net (code "55") (name "unconnected-(ARDUINO_NANO2-~{RESET}-Pad13)") (class "Default")
      (node (ref "ARDUINO_NANO2") (pin "13") (pinfunction "~{RESET}_13") (pintype "input"))
    )
    (net (code "56") (name "unconnected-(ARDUINO_NANO2-~{RESET}-Pad18)") (class "Default")
      (node (ref "ARDUINO_NANO2") (pin "18") (pinfunction "~{RESET}_18") (pintype "input"))
    )
    (net (code "57") (name "unconnected-(U2-LV-Pad6)") (class "Default")
      (node (ref "U2") (pin "6") (pinfunction "LV_6") (pintype "passive"))
    )
    (net (code "58") (name "unconnected-(U2-NC-Pad1)") (class "Default")
      (node (ref "U2") (pin "1") (pinfunction "NC_1") (pintype "no_connect"))
    )
    (net (code "59") (name "unconnected-(U2-OSC-Pad7)") (class "Default")
      (node (ref "U2") (pin "7") (pinfunction "OSC_7") (pintype "input"))
    )
  )
)
